# Rx_ckt_1.net
KiCad netlist of a schematic drawn in EAGLE
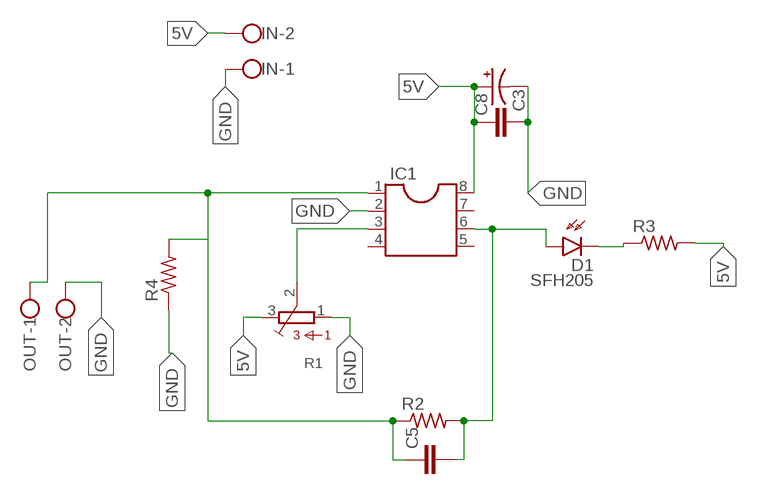
[diagram p0: schematic, sheet 1]

(export (version "E")
  (design (tool "Eeschema 10.0.6"))
  (components
    (comp (ref "C3")
      (value "C-EU050-025X075")
      (footprint "eagle-import:C050-025X075")
      (libsource (lib "eagle-import") (part "C-EU050-025X075"))
    )
    (comp (ref "C5")
      (value "C-EU050-025X075")
      (footprint "eagle-import:C050-025X075")
      (libsource (lib "eagle-import") (part "C-EU050-025X075"))
    )
    (comp (ref "C8")
      (value "CPOL-USE2.5-7")
      (footprint "eagle-import:E2,5-7")
      (libsource (lib "eagle-import") (part "CPOL-USE2.5-7"))
    )
    (comp (ref "D1")
      (value "SFH205")
      (footprint "eagle-import:SFH205")
      (libsource (lib "eagle-import") (part "SFH205"))
    )
    (comp (ref "IC1")
      (value "DIL8")
      (footprint "eagle-import:DIL08")
      (libsource (lib "eagle-import") (part "DIL8"))
    )
    (comp (ref "IN")
      (value "W237-102")
      (footprint "eagle-import:W237-102")
      (fields (field (name "MPN") "237-102"))
      (libsource (lib "eagle-import") (part "W237-102"))
    )
    (comp (ref "OUT")
      (value "W237-102")
      (footprint "eagle-import:W237-102")
      (fields (field (name "MPN") "237-102"))
      (libsource (lib "eagle-import") (part "W237-102"))
    )
    (comp (ref "R1")
      (value "3386-F")
      (footprint "eagle-import:3386F")
      (libsource (lib "eagle-import") (part "3386-F"))
    )
    (comp (ref "R2")
      (value "R-US_0207/10")
      (footprint "eagle-import:0207_10")
      (libsource (lib "eagle-import") (part "R-US_0207/10"))
    )
    (comp (ref "R3")
      (value "R-US_0207/10")
      (footprint "eagle-import:0207_10")
      (libsource (lib "eagle-import") (part "R-US_0207/10"))
    )
    (comp (ref "R4")
      (value "R-US_0207/10")
      (footprint "eagle-import:0207_10")
      (libsource (lib "eagle-import") (part "R-US_0207/10"))
    )
  )
  (nets
    (net (code "1") (name "5V") (class "Default")
      (node (ref "C3") (pin "2") (pinfunction "2_2") (pintype "passive"))
      (node (ref "C8") (pin "+") (pinfunction "+_+") (pintype "passive"))
      (node (ref "IC1") (pin "8") (pinfunction "8_8") (pintype "passive"))
      (node (ref "IN") (pin "2") (pinfunction "KL_2") (pintype "passive"))
      (node (ref "R1") (pin "3") (pinfunction "3_3") (pintype "passive"))
      (node (ref "R3") (pin "2") (pinfunction "2_2") (pintype "passive"))
    )
    (net (code "2") (name "GND") (class "Default")
      (node (ref "C3") (pin "1") (pinfunction "1_1") (pintype "passive"))
      (node (ref "C8") (pin "-") (pinfunction "-_-") (pintype "passive"))
      (node (ref "IC1") (pin "2") (pinfunction "2_2") (pintype "passive"))
      (node (ref "IN") (pin "1") (pinfunction "KL_1") (pintype "passive"))
      (node (ref "OUT") (pin "2") (pinfunction "KL_2") (pintype "passive"))
      (node (ref "R1") (pin "1") (pinfunction "1_1") (pintype "passive"))
      (node (ref "R4") (pin "1") (pinfunction "1_1") (pintype "passive"))
    )
    (net (code "3") (name "Net-(C5-Pad2)") (class "Default")
      (node (ref "C5") (pin "2") (pinfunction "2_2") (pintype "passive"))
      (node (ref "D1") (pin "A") (pinfunction "A_A") (pintype "passive"))
      (node (ref "IC1") (pin "6") (pinfunction "6_6") (pintype "passive"))
      (node (ref "R2") (pin "2") (pinfunction "2_2") (pintype "passive"))
    )
    (net (code "4") (name "Net-(D1-C)") (class "Default")
      (node (ref "D1") (pin "K") (pinfunction "C_K") (pintype "passive"))
      (node (ref "R3") (pin "1") (pinfunction "1_1") (pintype "passive"))
    )
    (net (code "5") (name "Net-(IC1-Pad3)") (class "Default")
      (node (ref "IC1") (pin "3") (pinfunction "3_3") (pintype "passive"))
      (node (ref "R1") (pin "2") (pinfunction "2_2") (pintype "passive"))
    )
    (net (code "6") (name "Net-(OUTA-KL)") (class "Default")
      (node (ref "C5") (pin "1") (pinfunction "1_1") (pintype "passive"))
      (node (ref "IC1") (pin "1") (pinfunction "1_1") (pintype "passive"))
      (node (ref "OUT") (pin "1") (pinfunction "KL_1") (pintype "passive"))
      (node (ref "R2") (pin "1") (pinfunction "1_1") (pintype "passive"))
      (node (ref "R4") (pin "2") (pinfunction "2_2") (pintype "passive"))
    )
    (net (code "7") (name "unconnected-(IC1-Pad4)") (class "Default")
      (node (ref "IC1") (pin "4") (pinfunction "4_4") (pintype "passive"))
    )
    (net (code "8") (name "unconnected-(IC1-Pad5)") (class "Default")
      (node (ref "IC1") (pin "5") (pinfunction "5_5") (pintype "passive"))
    )
    (net (code "9") (name "unconnected-(IC1-Pad7)") (class "Default")
      (node (ref "IC1") (pin "7") (pinfunction "7_7") (pintype "passive"))
    )
  )
)
